# XBee.net
KiCad netlist of a schematic drawn in Altium Designer
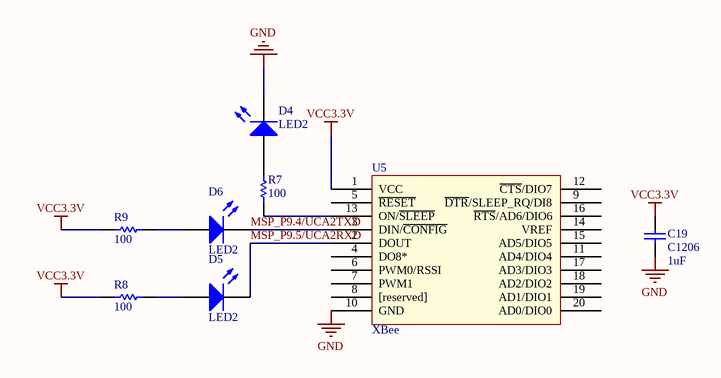
[diagram p0: XBee.SchDoc]

(export (version "E")
  (design (tool "Eeschema 10.0.6"))
  (components
    (comp (ref "C19")
      (value "C1206")
      (footprint "1206")
      (description "Ceramic Chip Capacitor - Standard")
      (fields (field (name "ALTIUM_VALUE") "1uF") (field (name "PUBLISHER") "Altium Limited"))
      (libsource (lib "KEMET Chip Capacitor") (part "C1206"))
    )
    (comp (ref "D4")
      (value "LED2")
      (footprint "LED_LiteOn:LED_LiteOn_footprint")
      (description "Typical RED, GREEN, YELLOW, AMBER GaAs LED")
      (libsource (lib "Miscellaneous Devices") (part "LED2"))
    )
    (comp (ref "D5")
      (value "LED2")
      (footprint "LED_LiteOn:LED_LiteOn_footprint")
      (description "Typical RED, GREEN, YELLOW, AMBER GaAs LED")
      (libsource (lib "Miscellaneous Devices") (part "LED2"))
    )
    (comp (ref "D6")
      (value "LED2")
      (footprint "LED_LiteOn:LED_LiteOn_footprint")
      (description "Typical RED, GREEN, YELLOW, AMBER GaAs LED")
      (libsource (lib "Miscellaneous Devices") (part "LED2"))
    )
    (comp (ref "R7")
      (value "100")
      (footprint "8-1206")
      (description "Thick Film Chip Resistor, 1 Ohm to 10M Ohm Range, 5% Tolerance, 1206 Size, 0.25 W")
      (fields (field (name "PUBLISHER") "Altium Limited"))
      (libsource (lib "Panasonic Resistor") (part "ERJ8GE"))
    )
    (comp (ref "R8")
      (value "100")
      (footprint "8-1206")
      (description "Thick Film Chip Resistor, 1 Ohm to 10M Ohm Range, 5% Tolerance, 1206 Size, 0.25 W")
      (fields (field (name "PUBLISHER") "Altium Limited"))
      (libsource (lib "Panasonic Resistor") (part "ERJ8GE"))
    )
    (comp (ref "R9")
      (value "100")
      (footprint "8-1206")
      (description "Thick Film Chip Resistor, 1 Ohm to 10M Ohm Range, 5% Tolerance, 1206 Size, 0.25 W")
      (fields (field (name "PUBLISHER") "Altium Limited"))
      (libsource (lib "Panasonic Resistor") (part "ERJ8GE"))
    )
    (comp (ref "U5") (value "XBee") (footprint "XBee:PCBComponent_1") (libsource (lib "XBee") (part "XBee")))
  )
  (nets
    (net (code "1") (name "/MSP_P9.4{slash}UCA2TXD") (class "Default")
      (node (ref "D6") (pin "2") (pinfunction "K_2") (pintype "passive"))
      (node (ref "U5") (pin "3") (pinfunction "DIN/~{CONFIG}_3") (pintype "passive"))
    )
    (net (code "2") (name "/MSP_P9.5{slash}UCA2RXD") (class "Default")
      (node (ref "D5") (pin "2") (pinfunction "K_2") (pintype "passive"))
      (node (ref "U5") (pin "2") (pinfunction "DOUT_2") (pintype "passive"))
    )
    (net (code "3") (name "GND") (class "Default")
      (node (ref "C19") (pin "1") (pinfunction "1_1") (pintype "passive"))
      (node (ref "D4") (pin "2") (pinfunction "K_2") (pintype "passive"))
      (node (ref "U5") (pin "10") (pinfunction "GND_10") (pintype "passive"))
    )
    (net (code "4") (name "Net-(D4-A)") (class "Default")
      (node (ref "D4") (pin "1") (pinfunction "A_1") (pintype "passive"))
      (node (ref "R7") (pin "1") (pinfunction "1_1") (pintype "passive"))
    )
    (net (code "5") (name "Net-(D5-A)") (class "Default")
      (node (ref "D5") (pin "1") (pinfunction "A_1") (pintype "passive"))
      (node (ref "R8") (pin "2") (pinfunction "2_2") (pintype "passive"))
    )
    (net (code "6") (name "Net-(D6-A)") (class "Default")
      (node (ref "D6") (pin "1") (pinfunction "A_1") (pintype "passive"))
      (node (ref "R9") (pin "2") (pinfunction "2_2") (pintype "passive"))
    )
    (net (code "7") (name "Net-(U5-ON{slash}~{SLEEP})") (class "Default")
      (node (ref "R7") (pin "2") (pinfunction "2_2") (pintype "passive"))
      (node (ref "U5") (pin "13") (pinfunction "ON/~{SLEEP}_13") (pintype "passive"))
    )
    (net (code "8") (name "VCC3.3V") (class "Default")
      (node (ref "C19") (pin "2") (pinfunction "2_2") (pintype "passive"))
      (node (ref "R8") (pin "1") (pinfunction "1_1") (pintype "passive"))
      (node (ref "R9") (pin "1") (pinfunction "1_1") (pintype "passive"))
      (node (ref "U5") (pin "1") (pinfunction "VCC_1") (pintype "passive"))
    )
    (net (code "9") (name "unconnected-(U5-AD0{slash}DIO0-Pad20)") (class "Default")
      (node (ref "U5") (pin "20") (pinfunction "AD0/DIO0_20") (pintype "passive"))
    )
    (net (code "10") (name "unconnected-(U5-AD1{slash}DIO1-Pad19)") (class "Default")
      (node (ref "U5") (pin "19") (pinfunction "AD1/DIO1_19") (pintype "passive"))
    )
    (net (code "11") (name "unconnected-(U5-AD2{slash}DIO2-Pad18)") (class "Default")
      (node (ref "U5") (pin "18") (pinfunction "AD2/DIO2_18") (pintype "passive"))
    )
    (net (code "12") (name "unconnected-(U5-AD3{slash}DIO3-Pad17)") (class "Default")
      (node (ref "U5") (pin "17") (pinfunction "AD3/DIO3_17") (pintype "passive"))
    )
    (net (code "13") (name "unconnected-(U5-AD4{slash}DIO4-Pad11)") (class "Default")
      (node (ref "U5") (pin "11") (pinfunction "AD4/DIO4_11") (pintype "passive"))
    )
    (net (code "14") (name "unconnected-(U5-AD5{slash}DIO5-Pad15)") (class "Default")
      (node (ref "U5") (pin "15") (pinfunction "AD5/DIO5_15") (pintype "passive"))
    )
    (net (code "15") (name "unconnected-(U5-DO8*-Pad4)") (class "Default")
      (node (ref "U5") (pin "4") (pinfunction "DO8*_4") (pintype "passive"))
    )
    (net (code "16") (name "unconnected-(U5-PWM0{slash}RSSI-Pad6)") (class "Default")
      (node (ref "U5") (pin "6") (pinfunction "PWM0/RSSI_6") (pintype "passive"))
    )
    (net (code "17") (name "unconnected-(U5-PWM1-Pad7)") (class "Default")
      (node (ref "U5") (pin "7") (pinfunction "PWM1_7") (pintype "passive"))
    )
    (net (code "18") (name "unconnected-(U5-VREF-Pad14)") (class "Default")
      (node (ref "U5") (pin "14") (pinfunction "VREF_14") (pintype "passive"))
    )
    (net (code "19") (name "unconnected-(U5-[reserved]-Pad8)") (class "Default")
      (node (ref "U5") (pin "8") (pinfunction "[reserved]_8") (pintype "passive"))
    )
    (net (code "20") (name "unconnected-(U5-~{CTS}{slash}DIO7-Pad12)") (class "Default")
      (node (ref "U5") (pin "12") (pinfunction "~{CTS}/DIO7_12") (pintype "passive"))
    )
    (net (code "21") (name "unconnected-(U5-~{DTR}{slash}SLEEP_RQ{slash}DI8-Pad9)") (class "Default")
      (node (ref "U5") (pin "9") (pinfunction "~{DTR}/SLEEP_RQ/DI8_9") (pintype "passive"))
    )
    (net (code "22") (name "unconnected-(U5-~{RESET}-Pad5)") (class "Default")
      (node (ref "U5") (pin "5") (pinfunction "~{RESET}_5") (pintype "passive"))
    )
    (net (code "23") (name "unconnected-(U5-~{RTS}{slash}AD6{slash}DIO6-Pad16)") (class "Default")
      (node (ref "U5") (pin "16") (pinfunction "~{RTS}/AD6/DIO6_16") (pintype "passive"))
    )
  )
)
